# pid_interface_w_term.net
KiCad netlist of a schematic drawn in EAGLE
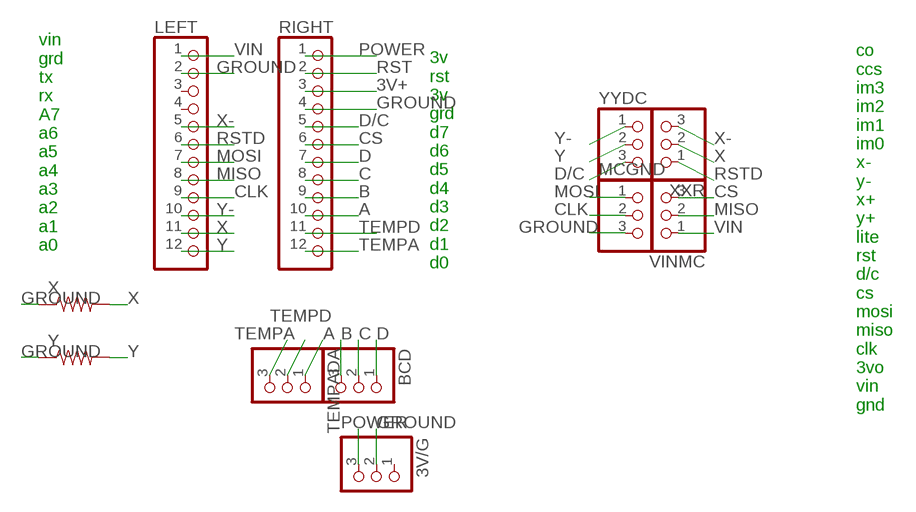
[diagram p0: schematic, sheet 1]

(export (version "E")
  (design (tool "Eeschema 10.0.6"))
  (components
    (comp (ref "3V/G")
      (value "PINHD-1X3CB")
      (footprint "eagle-import:1X03-CLEANBIG")
      (libsource (lib "eagle-import") (part "PINHD-1X3CB"))
    )
    (comp (ref "BCD")
      (value "PINHD-1X3CB")
      (footprint "eagle-import:1X03-CLEANBIG")
      (libsource (lib "eagle-import") (part "PINHD-1X3CB"))
    )
    (comp (ref "LEFT")
      (value "PINHD-1X12-CB")
      (footprint "eagle-import:1X12-CB")
      (libsource (lib "eagle-import") (part "PINHD-1X12-CB"))
    )
    (comp (ref "MCGND")
      (value "PINHD-1X3CB")
      (footprint "eagle-import:1X03-CLEANBIG")
      (libsource (lib "eagle-import") (part "PINHD-1X3CB"))
    )
    (comp (ref "RIGHT")
      (value "PINHD-1X12-CB")
      (footprint "eagle-import:1X12-CB")
      (libsource (lib "eagle-import") (part "PINHD-1X12-CB"))
    )
    (comp (ref "TEMPADA")
      (value "PINHD-1X3CB")
      (footprint "eagle-import:1X03-CLEANBIG")
      (libsource (lib "eagle-import") (part "PINHD-1X3CB"))
    )
    (comp (ref "VINMC")
      (value "PINHD-1X3CB")
      (footprint "eagle-import:1X03-CLEANBIG")
      (libsource (lib "eagle-import") (part "PINHD-1X3CB"))
    )
    (comp (ref "X")
      (value "10KOHM-1/6W-5%(PTH)KIT")
      (footprint "eagle-import:AXIAL-0.3-KIT")
      (libsource (lib "eagle-import") (part "10KOHM-1/6W-5%(PTH)KIT"))
    )
    (comp (ref "XXR")
      (value "PINHD-1X3CB")
      (footprint "eagle-import:1X03-CLEANBIG")
      (libsource (lib "eagle-import") (part "PINHD-1X3CB"))
    )
    (comp (ref "Y")
      (value "10KOHM-1/6W-5%(PTH)KIT")
      (footprint "eagle-import:AXIAL-0.3-KIT")
      (libsource (lib "eagle-import") (part "10KOHM-1/6W-5%(PTH)KIT"))
    )
    (comp (ref "YYDC")
      (value "PINHD-1X3CB")
      (footprint "eagle-import:1X03-CLEANBIG")
      (libsource (lib "eagle-import") (part "PINHD-1X3CB"))
    )
  )
  (nets
    (net (code "1") (name "/3V+") (class "Default")
      (node (ref "RIGHT") (pin "3") (pinfunction "3_3") (pintype "passive"))
    )
    (net (code "2") (name "/A") (class "Default")
      (node (ref "RIGHT") (pin "10") (pinfunction "10_10") (pintype "passive"))
      (node (ref "TEMPADA") (pin "1") (pinfunction "1_1") (pintype "passive"))
    )
    (net (code "3") (name "/B") (class "Default")
      (node (ref "BCD") (pin "3") (pinfunction "3_3") (pintype "passive"))
      (node (ref "RIGHT") (pin "9") (pinfunction "9_9") (pintype "passive"))
    )
    (net (code "4") (name "/C") (class "Default")
      (node (ref "BCD") (pin "2") (pinfunction "2_2") (pintype "passive"))
      (node (ref "RIGHT") (pin "8") (pinfunction "8_8") (pintype "passive"))
    )
    (net (code "5") (name "/CLK") (class "Default")
      (node (ref "LEFT") (pin "9") (pinfunction "9_9") (pintype "passive"))
      (node (ref "MCGND") (pin "2") (pinfunction "2_2") (pintype "passive"))
    )
    (net (code "6") (name "/CS") (class "Default")
      (node (ref "RIGHT") (pin "6") (pinfunction "6_6") (pintype "passive"))
      (node (ref "VINMC") (pin "3") (pinfunction "3_3") (pintype "passive"))
    )
    (net (code "7") (name "/D") (class "Default")
      (node (ref "BCD") (pin "1") (pinfunction "1_1") (pintype "passive"))
      (node (ref "RIGHT") (pin "7") (pinfunction "7_7") (pintype "passive"))
    )
    (net (code "8") (name "/D{slash}C") (class "Default")
      (node (ref "RIGHT") (pin "5") (pinfunction "5_5") (pintype "passive"))
      (node (ref "YYDC") (pin "3") (pinfunction "3_3") (pintype "passive"))
    )
    (net (code "9") (name "/GROUND") (class "Default")
      (node (ref "3V/G") (pin "2") (pinfunction "2_2") (pintype "passive"))
      (node (ref "LEFT") (pin "2") (pinfunction "2_2") (pintype "passive"))
      (node (ref "MCGND") (pin "3") (pinfunction "3_3") (pintype "passive"))
      (node (ref "RIGHT") (pin "4") (pinfunction "4_4") (pintype "passive"))
      (node (ref "X") (pin "P$1") (pinfunction "1_P$1") (pintype "passive"))
      (node (ref "Y") (pin "P$1") (pinfunction "1_P$1") (pintype "passive"))
    )
    (net (code "10") (name "/MISO") (class "Default")
      (node (ref "LEFT") (pin "8") (pinfunction "8_8") (pintype "passive"))
      (node (ref "VINMC") (pin "2") (pinfunction "2_2") (pintype "passive"))
    )
    (net (code "11") (name "/MOSI") (class "Default")
      (node (ref "LEFT") (pin "7") (pinfunction "7_7") (pintype "passive"))
      (node (ref "MCGND") (pin "1") (pinfunction "1_1") (pintype "passive"))
    )
    (net (code "12") (name "/POWER") (class "Default")
      (node (ref "3V/G") (pin "3") (pinfunction "3_3") (pintype "passive"))
      (node (ref "RIGHT") (pin "1") (pinfunction "1_1") (pintype "passive"))
    )
    (net (code "13") (name "/RST") (class "Default")
      (node (ref "RIGHT") (pin "2") (pinfunction "2_2") (pintype "passive"))
    )
    (net (code "14") (name "/RSTD") (class "Default")
      (node (ref "LEFT") (pin "6") (pinfunction "6_6") (pintype "passive"))
      (node (ref "XXR") (pin "1") (pinfunction "1_1") (pintype "passive"))
    )
    (net (code "15") (name "/TEMPA") (class "Default")
      (node (ref "RIGHT") (pin "12") (pinfunction "12_12") (pintype "passive"))
      (node (ref "TEMPADA") (pin "3") (pinfunction "3_3") (pintype "passive"))
    )
    (net (code "16") (name "/TEMPD") (class "Default")
      (node (ref "RIGHT") (pin "11") (pinfunction "11_11") (pintype "passive"))
      (node (ref "TEMPADA") (pin "2") (pinfunction "2_2") (pintype "passive"))
    )
    (net (code "17") (name "/VIN") (class "Default")
      (node (ref "LEFT") (pin "1") (pinfunction "1_1") (pintype "passive"))
      (node (ref "VINMC") (pin "1") (pinfunction "1_1") (pintype "passive"))
    )
    (net (code "18") (name "/X") (class "Default")
      (node (ref "LEFT") (pin "11") (pinfunction "11_11") (pintype "passive"))
      (node (ref "X") (pin "P$2") (pinfunction "2_P$2") (pintype "passive"))
      (node (ref "XXR") (pin "2") (pinfunction "2_2") (pintype "passive"))
    )
    (net (code "19") (name "/X-") (class "Default")
      (node (ref "LEFT") (pin "5") (pinfunction "5_5") (pintype "passive"))
      (node (ref "XXR") (pin "3") (pinfunction "3_3") (pintype "passive"))
    )
    (net (code "20") (name "/Y") (class "Default")
      (node (ref "LEFT") (pin "12") (pinfunction "12_12") (pintype "passive"))
      (node (ref "Y") (pin "P$2") (pinfunction "2_P$2") (pintype "passive"))
      (node (ref "YYDC") (pin "2") (pinfunction "2_2") (pintype "passive"))
    )
    (net (code "21") (name "/Y-") (class "Default")
      (node (ref "LEFT") (pin "10") (pinfunction "10_10") (pintype "passive"))
      (node (ref "YYDC") (pin "1") (pinfunction "1_1") (pintype "passive"))
    )
    (net (code "22") (name "unconnected-(3V/G-Pad1)") (class "Default")
      (node (ref "3V/G") (pin "1") (pinfunction "1_1") (pintype "passive"))
    )
    (net (code "23") (name "unconnected-(LEFT-Pad3)") (class "Default")
      (node (ref "LEFT") (pin "3") (pinfunction "3_3") (pintype "passive"))
    )
    (net (code "24") (name "unconnected-(LEFT-Pad4)") (class "Default")
      (node (ref "LEFT") (pin "4") (pinfunction "4_4") (pintype "passive"))
    )
  )
)
